# ESP32.net
KiCad netlist of a schematic drawn in Altium Designer
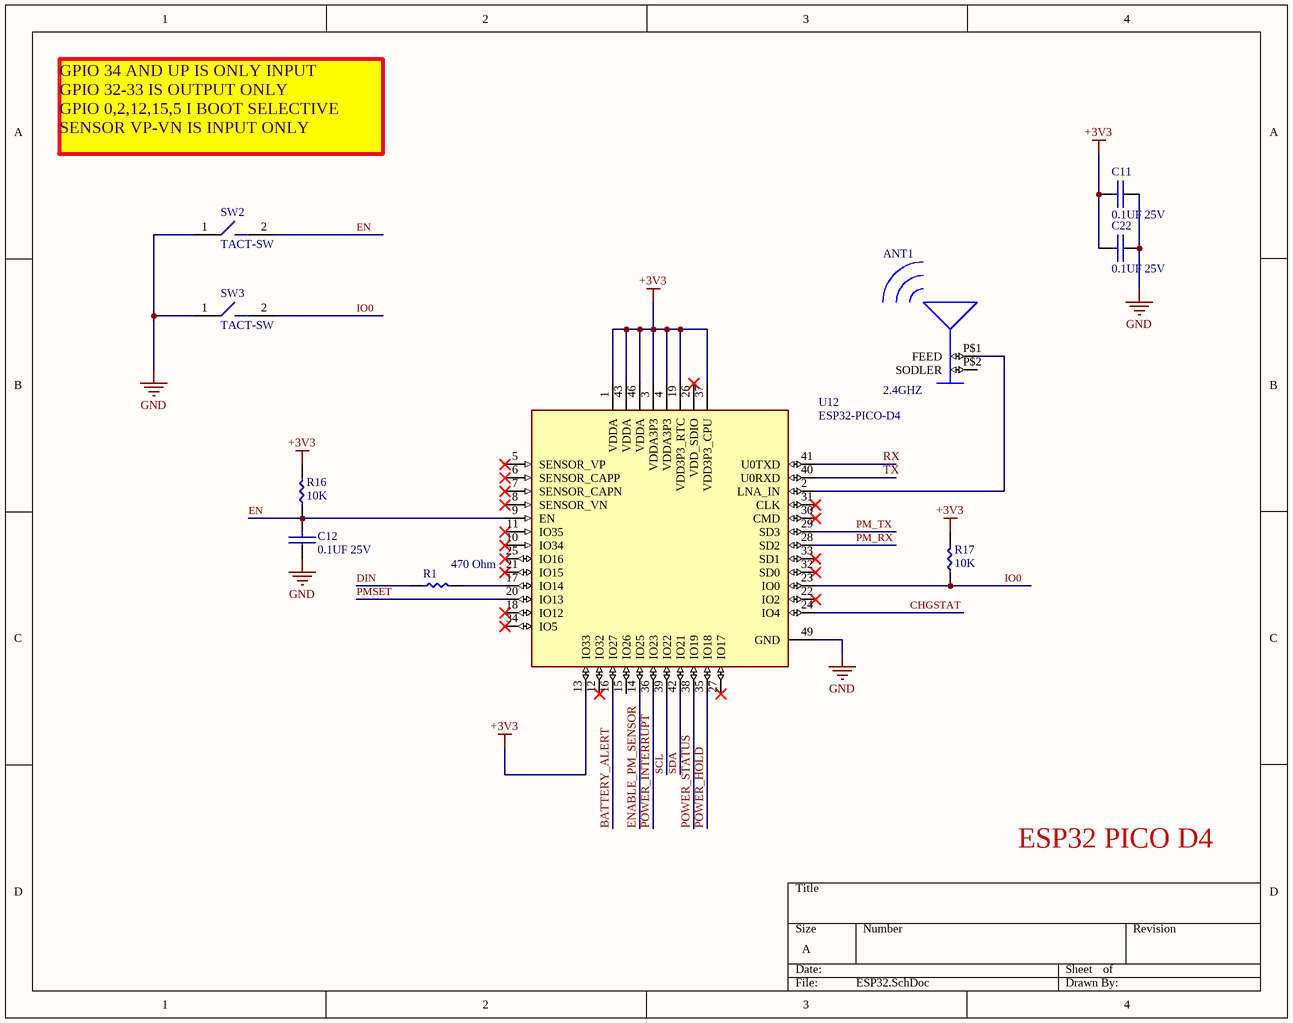
[diagram p0: ESP32.SchDoc]

(export (version "E")
  (design (tool "Eeschema 10.0.6"))
  (components
    (comp (ref "ANT1")
      (value "2.4GHZ")
      (footprint "AN2051")
      (description "SMD Built-in Antenna 2.4GHz")
      (fields (field (name "MF") "RainSun") (field (name "MP") "AN2051"))
      (libsource (lib "salcox") (part "AN2051"))
    )
    (comp (ref "C11")
      (value "0.1UF 25V")
      (footprint "C0603")
      (description "CAP CER 0.1UF 25V X5R 0603")
      (fields
        (field (name "MANUFACTURER") "Kyocera AVX")
        (field (name "MANUFACTURER PART NUMBER") "06033D104KAT2A")
      )
      (libsource (lib "salcox") (part "06033D104KAT2A"))
    )
    (comp (ref "C12")
      (value "0.1UF 25V")
      (footprint "C0603")
      (description "CAP CER 0.1UF 25V X5R 0603")
      (fields
        (field (name "MANUFACTURER") "Kyocera AVX")
        (field (name "MANUFACTURER PART NUMBER") "06033D104KAT2A")
      )
      (libsource (lib "salcox") (part "06033D104KAT2A"))
    )
    (comp (ref "C22")
      (value "0.1UF 25V")
      (footprint "C0603")
      (description "CAP CER 0.1UF 25V X5R 0603")
      (fields
        (field (name "MANUFACTURER") "Kyocera AVX")
        (field (name "MANUFACTURER PART NUMBER") "06033D104KAT2A")
      )
      (libsource (lib "salcox") (part "06033D104KAT2A"))
    )
    (comp (ref "R1")
      (value "470 Ohm")
      (footprint "R0603")
      (description "SMD Resistor, Thick film 470 Ohm,  ±  1 %, 0603, CRCW0603470RFKEA, Vishay")
      (fields
        (field (name "MANUFACTURER") "Vishay")
        (field (name "MANUFACTURER PART NUMBER") "CRCW0603-470RFKEA")
      )
      (libsource (lib "salcox") (part "CRCW0603-470RFKEA"))
    )
    (comp (ref "R16")
      (value "10K")
      (footprint "R0603")
      (description "RES SMD 10K OHM 1% 1/10W 0603")
      (fields
        (field (name "MANUFACTURER") "Yageo")
        (field (name "MANUFACTURER PART NUMBER") "RC0603FR-0710KL")
      )
      (libsource (lib "salcox") (part "RC0603FR-0710KL"))
    )
    (comp (ref "R17")
      (value "10K")
      (footprint "R0603")
      (description "RES SMD 10K OHM 1% 1/10W 0603")
      (fields
        (field (name "MANUFACTURER") "Yageo")
        (field (name "MANUFACTURER PART NUMBER") "RC0603FR-0710KL")
      )
      (libsource (lib "salcox") (part "RC0603FR-0710KL"))
    )
    (comp (ref "SW2")
      (value "TACT-SW")
      (footprint "kmr7-switch")
      (description "switch")
      (fields (field (name "MANUFACTURER") "ITT C&K") (field (name "MANUFACTURER PART NUMBER") "KMR731NGLFS"))
      (libsource (lib "salcox") (part "KMR731NGLFS"))
    )
    (comp (ref "SW3")
      (value "TACT-SW")
      (footprint "kmr7-switch")
      (description "switch")
      (fields (field (name "MANUFACTURER") "ITT C&K") (field (name "MANUFACTURER PART NUMBER") "KMR731NGLFS"))
      (libsource (lib "salcox") (part "KMR731NGLFS"))
    )
    (comp (ref "U12")
      (value "ESP32-PICO-D4")
      (footprint "PQFN50P700X700X104-49N")
      (fields (field (name "MF") "Espressif Systems"))
      (libsource (lib "salcox") (part "ESP32-PICO-D4"))
    )
  )
  (nets
    (net (code "1") (name "+3V3") (class "Default")
      (node (ref "C11") (pin "2") (pinfunction "2_2") (pintype "passive"))
      (node (ref "C22") (pin "2") (pinfunction "2_2") (pintype "passive"))
      (node (ref "R16") (pin "2") (pinfunction "2_2") (pintype "passive"))
      (node (ref "R17") (pin "2") (pinfunction "2_2") (pintype "passive"))
      (node (ref "U12") (pin "1") (pinfunction "VDDA_1") (pintype "power_in"))
      (node (ref "U12") (pin "13") (pinfunction "IO33_13") (pintype "bidirectional"))
      (node (ref "U12") (pin "19") (pinfunction "VDD3P3_RTC_19") (pintype "power_in"))
      (node (ref "U12") (pin "3") (pinfunction "VDDA3P3_3") (pintype "power_in"))
      (node (ref "U12") (pin "37") (pinfunction "VDD3P3_CPU_37") (pintype "power_in"))
      (node (ref "U12") (pin "4") (pinfunction "VDDA3P3_4") (pintype "power_in"))
      (node (ref "U12") (pin "43") (pinfunction "VDDA_43") (pintype "power_in"))
      (node (ref "U12") (pin "46") (pinfunction "VDDA_46") (pintype "power_in"))
    )
    (net (code "2") (name "/BATTERY_ALERT") (class "Default")
      (node (ref "U12") (pin "16") (pinfunction "IO27_16") (pintype "bidirectional"))
    )
    (net (code "3") (name "/CHGSTAT") (class "Default")
      (node (ref "U12") (pin "24") (pinfunction "IO4_24") (pintype "bidirectional"))
    )
    (net (code "4") (name "/DIN") (class "Default")
      (node (ref "R1") (pin "1") (pinfunction "1_1") (pintype "passive"))
    )
    (net (code "5") (name "/EN") (class "Default")
      (node (ref "C12") (pin "2") (pinfunction "2_2") (pintype "passive"))
      (node (ref "R16") (pin "1") (pinfunction "1_1") (pintype "passive"))
      (node (ref "SW2") (pin "2") (pintype "passive"))
      (node (ref "U12") (pin "9") (pinfunction "EN_9") (pintype "input"))
    )
    (net (code "6") (name "/ENABLE_PM_SENSOR") (class "Default")
      (node (ref "U12") (pin "14") (pinfunction "IO25_14") (pintype "bidirectional"))
    )
    (net (code "7") (name "/IO0") (class "Default")
      (node (ref "R17") (pin "1") (pinfunction "1_1") (pintype "passive"))
      (node (ref "SW3") (pin "2") (pintype "passive"))
      (node (ref "U12") (pin "23") (pinfunction "IO0_23") (pintype "bidirectional"))
    )
    (net (code "8") (name "/PMSET") (class "Default")
      (node (ref "U12") (pin "20") (pinfunction "IO13_20") (pintype "bidirectional"))
    )
    (net (code "9") (name "/PM_RX") (class "Default")
      (node (ref "U12") (pin "28") (pinfunction "SD2_28") (pintype "bidirectional"))
    )
    (net (code "10") (name "/PM_TX") (class "Default")
      (node (ref "U12") (pin "29") (pinfunction "SD3_29") (pintype "bidirectional"))
    )
    (net (code "11") (name "/POWER_HOLD") (class "Default")
      (node (ref "U12") (pin "35") (pinfunction "IO18_35") (pintype "bidirectional"))
    )
    (net (code "12") (name "/POWER_INTERRUPT") (class "Default")
      (node (ref "U12") (pin "36") (pinfunction "IO23_36") (pintype "bidirectional"))
    )
    (net (code "13") (name "/POWER_STATUS") (class "Default")
      (node (ref "U12") (pin "38") (pinfunction "IO19_38") (pintype "bidirectional"))
    )
    (net (code "14") (name "/RX") (class "Default")
      (node (ref "U12") (pin "41") (pinfunction "U0TXD_41") (pintype "bidirectional"))
    )
    (net (code "15") (name "/SCL") (class "Default")
      (node (ref "U12") (pin "39") (pinfunction "IO22_39") (pintype "bidirectional"))
    )
    (net (code "16") (name "/SDA") (class "Default")
      (node (ref "U12") (pin "42") (pinfunction "IO21_42") (pintype "bidirectional"))
    )
    (net (code "17") (name "/TX") (class "Default")
      (node (ref "U12") (pin "40") (pinfunction "U0RXD_40") (pintype "bidirectional"))
    )
    (net (code "18") (name "GND") (class "Default")
      (node (ref "C11") (pin "1") (pinfunction "1_1") (pintype "passive"))
      (node (ref "C12") (pin "1") (pinfunction "1_1") (pintype "passive"))
      (node (ref "C22") (pin "1") (pinfunction "1_1") (pintype "passive"))
      (node (ref "SW2") (pin "1") (pintype "passive"))
      (node (ref "SW3") (pin "1") (pintype "passive"))
      (node (ref "U12") (pin "49") (pinfunction "GND_49") (pintype "power_in"))
    )
    (net (code "19") (name "Net-(ANT1-FEED)") (class "Default")
      (node (ref "ANT1") (pin "P$1") (pinfunction "FEED_P$1") (pintype "bidirectional"))
      (node (ref "U12") (pin "2") (pinfunction "LNA_IN_2") (pintype "bidirectional"))
    )
    (net (code "20") (name "Net-(U12-IO14)") (class "Default")
      (node (ref "R1") (pin "2") (pinfunction "2_2") (pintype "passive"))
      (node (ref "U12") (pin "17") (pinfunction "IO14_17") (pintype "bidirectional"))
    )
    (net (code "21") (name "unconnected-(ANT1-SODLER-PadP$2)") (class "Default")
      (node (ref "ANT1") (pin "P$2") (pinfunction "SODLER_P$2") (pintype "bidirectional"))
    )
    (net (code "22") (name "unconnected-(U12-CLK-Pad31)") (class "Default")
      (node (ref "U12") (pin "31") (pinfunction "CLK_31") (pintype "bidirectional+no_connect"))
    )
    (net (code "23") (name "unconnected-(U12-CMD-Pad30)") (class "Default")
      (node (ref "U12") (pin "30") (pinfunction "CMD_30") (pintype "bidirectional+no_connect"))
    )
    (net (code "24") (name "unconnected-(U12-IO2-Pad22)") (class "Default")
      (node (ref "U12") (pin "22") (pinfunction "IO2_22") (pintype "bidirectional+no_connect"))
    )
    (net (code "25") (name "unconnected-(U12-IO5-Pad34)") (class "Default")
      (node (ref "U12") (pin "34") (pinfunction "IO5_34") (pintype "bidirectional+no_connect"))
    )
    (net (code "26") (name "unconnected-(U12-IO12-Pad18)") (class "Default")
      (node (ref "U12") (pin "18") (pinfunction "IO12_18") (pintype "bidirectional+no_connect"))
    )
    (net (code "27") (name "unconnected-(U12-IO15-Pad21)") (class "Default")
      (node (ref "U12") (pin "21") (pinfunction "IO15_21") (pintype "bidirectional+no_connect"))
    )
    (net (code "28") (name "unconnected-(U12-IO16-Pad25)") (class "Default")
      (node (ref "U12") (pin "25") (pinfunction "IO16_25") (pintype "bidirectional+no_connect"))
    )
    (net (code "29") (name "unconnected-(U12-IO17-Pad27)") (class "Default")
      (node (ref "U12") (pin "27") (pinfunction "IO17_27") (pintype "bidirectional+no_connect"))
    )
    (net (code "30") (name "unconnected-(U12-IO26-Pad15)") (class "Default")
      (node (ref "U12") (pin "15") (pinfunction "IO26_15") (pintype "bidirectional"))
    )
    (net (code "31") (name "unconnected-(U12-IO32-Pad12)") (class "Default")
      (node (ref "U12") (pin "12") (pinfunction "IO32_12") (pintype "bidirectional+no_connect"))
    )
    (net (code "32") (name "unconnected-(U12-IO34-Pad10)") (class "Default")
      (node (ref "U12") (pin "10") (pinfunction "IO34_10") (pintype "input+no_connect"))
    )
    (net (code "33") (name "unconnected-(U12-IO35-Pad11)") (class "Default")
      (node (ref "U12") (pin "11") (pinfunction "IO35_11") (pintype "input+no_connect"))
    )
    (net (code "34") (name "unconnected-(U12-SD0-Pad32)") (class "Default")
      (node (ref "U12") (pin "32") (pinfunction "SD0_32") (pintype "bidirectional+no_connect"))
    )
    (net (code "35") (name "unconnected-(U12-SD1-Pad33)") (class "Default")
      (node (ref "U12") (pin "33") (pinfunction "SD1_33") (pintype "bidirectional+no_connect"))
    )
    (net (code "36") (name "unconnected-(U12-SENSOR_CAPN-Pad7)") (class "Default")
      (node (ref "U12") (pin "7") (pinfunction "SENSOR_CAPN_7") (pintype "input+no_connect"))
    )
    (net (code "37") (name "unconnected-(U12-SENSOR_CAPP-Pad6)") (class "Default")
      (node (ref "U12") (pin "6") (pinfunction "SENSOR_CAPP_6") (pintype "input+no_connect"))
    )
    (net (code "38") (name "unconnected-(U12-SENSOR_VN-Pad8)") (class "Default")
      (node (ref "U12") (pin "8") (pinfunction "SENSOR_VN_8") (pintype "input+no_connect"))
    )
    (net (code "39") (name "unconnected-(U12-SENSOR_VP-Pad5)") (class "Default")
      (node (ref "U12") (pin "5") (pinfunction "SENSOR_VP_5") (pintype "input+no_connect"))
    )
    (net (code "40") (name "unconnected-(U12-VDD_SDIO-Pad26)") (class "Default")
      (node (ref "U12") (pin "26") (pinfunction "VDD_SDIO_26") (pintype "power_in+no_connect"))
    )
  )
)
